# CAN_controller_trancs.net
KiCad netlist of a schematic drawn in Altium Designer
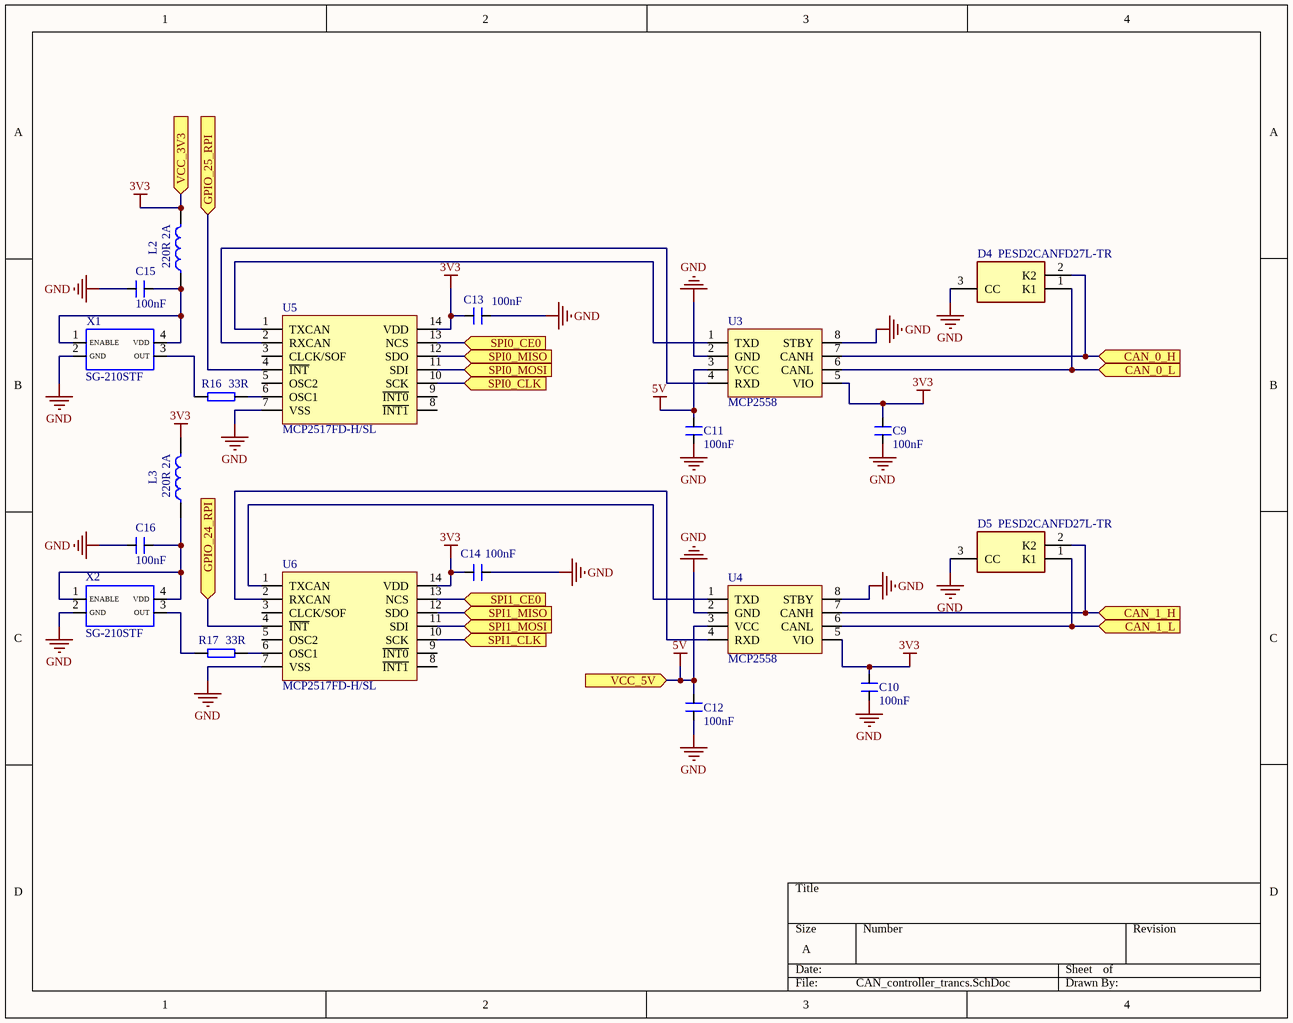
[diagram p0: CAN_controller_trancs.SchDoc]

(export (version "E")
  (design (tool "Eeschema 10.0.6"))
  (components
    (comp (ref "C9") (value "100nF") (footprint "CAP_0805") (libsource (lib "sch_comp") (part "CAP_0805")))
    (comp (ref "C10") (value "100nF") (footprint "CAP_0805") (libsource (lib "sch_comp") (part "CAP_0805")))
    (comp (ref "C11") (value "100nF") (footprint "CAP_0805") (libsource (lib "sch_comp") (part "CAP_0805")))
    (comp (ref "C12") (value "100nF") (footprint "CAP_0805") (libsource (lib "sch_comp") (part "CAP_0805")))
    (comp (ref "C13") (value "100nF") (footprint "CAP_0805") (libsource (lib "sch_comp") (part "CAP_0805")))
    (comp (ref "C14") (value "100nF") (footprint "CAP_0805") (libsource (lib "sch_comp") (part "CAP_0805")))
    (comp (ref "C15") (value "100nF") (footprint "CAP_0805") (libsource (lib "sch_comp") (part "CAP_0805")))
    (comp (ref "C16") (value "100nF") (footprint "CAP_0805") (libsource (lib "sch_comp") (part "CAP_0805")))
    (comp (ref "D4")
      (value "PESD2CANFD27L-TR")
      (footprint "SamacSys:SOT95P230X110-3N")
      (description "Diode")
      (fields (field (name "MOUSER PART NUMBER") "771-PESD2CANFD27L-TR"))
      (libsource (lib "*") (part "PESD2CANFD27L-TR"))
    )
    (comp (ref "D5")
      (value "PESD2CANFD27L-TR")
      (footprint "SamacSys:SOT95P230X110-3N")
      (description "Diode")
      (fields (field (name "MOUSER PART NUMBER") "771-PESD2CANFD27L-TR"))
      (libsource (lib "*") (part "PESD2CANFD27L-TR"))
    )
    (comp (ref "L2") (value "220R 2A") (footprint "L_0805") (libsource (lib "sch_comp") (part "Inductor")))
    (comp (ref "L3") (value "220R 2A") (footprint "L_0805") (libsource (lib "sch_comp") (part "Inductor")))
    (comp (ref "R16") (value "33R") (footprint "RES0402") (libsource (lib "sch_comp") (part "RES 0402")))
    (comp (ref "R17") (value "33R") (footprint "RES0402") (libsource (lib "sch_comp") (part "RES 0402")))
    (comp (ref "U3")
      (value "MCP2558")
      (footprint "MCP2557_SOIC8")
      (libsource (lib "sch_comp") (part "MCP2558"))
    )
    (comp (ref "U4")
      (value "MCP2558")
      (footprint "MCP2557_SOIC8")
      (libsource (lib "sch_comp") (part "MCP2558"))
    )
    (comp (ref "U5")
      (value "MCP2517FD-H/SL")
      (footprint "MCP2517FD_SOIC14")
      (libsource (lib "sch_comp") (part "MCP2517FD-H/SL"))
    )
    (comp (ref "U6")
      (value "MCP2517FD-H/SL")
      (footprint "MCP2517FD_SOIC14")
      (libsource (lib "sch_comp") (part "MCP2517FD-H/SL"))
    )
    (comp (ref "X1") (value "SG-210STF") (footprint "Osc") (libsource (lib "sch_comp") (part "SG-210STF")))
    (comp (ref "X2") (value "SG-210STF") (footprint "Osc") (libsource (lib "sch_comp") (part "SG-210STF")))
  )
  (nets
    (net (code "1") (name "/CAN_0_H") (class "Default")
      (node (ref "D4") (pin "2") (pinfunction "K2_2") (pintype "passive"))
      (node (ref "U3") (pin "7") (pinfunction "CANH_7") (pintype "passive"))
    )
    (net (code "2") (name "/CAN_0_L") (class "Default")
      (node (ref "D4") (pin "1") (pinfunction "K1_1") (pintype "passive"))
      (node (ref "U3") (pin "6") (pinfunction "CANL_6") (pintype "passive"))
    )
    (net (code "3") (name "/CAN_1_H") (class "Default")
      (node (ref "D5") (pin "2") (pinfunction "K2_2") (pintype "passive"))
      (node (ref "U4") (pin "7") (pinfunction "CANH_7") (pintype "passive"))
    )
    (net (code "4") (name "/CAN_1_L") (class "Default")
      (node (ref "D5") (pin "1") (pinfunction "K1_1") (pintype "passive"))
      (node (ref "U4") (pin "6") (pinfunction "CANL_6") (pintype "passive"))
    )
    (net (code "5") (name "/GPIO_24_RPI") (class "Default")
      (node (ref "U6") (pin "4") (pinfunction "~{INT}_4") (pintype "passive"))
    )
    (net (code "6") (name "/GPIO_25_RPI") (class "Default")
      (node (ref "U5") (pin "4") (pinfunction "~{INT}_4") (pintype "passive"))
    )
    (net (code "7") (name "/SPI0_CE0") (class "Default")
      (node (ref "U5") (pin "13") (pinfunction "NCS_13") (pintype "passive"))
    )
    (net (code "8") (name "/SPI0_CLK") (class "Default")
      (node (ref "U5") (pin "10") (pinfunction "SCK_10") (pintype "passive"))
    )
    (net (code "9") (name "/SPI0_MISO") (class "Default")
      (node (ref "U5") (pin "12") (pinfunction "SDO_12") (pintype "passive"))
    )
    (net (code "10") (name "/SPI0_MOSI") (class "Default")
      (node (ref "U5") (pin "11") (pinfunction "SDI_11") (pintype "passive"))
    )
    (net (code "11") (name "/SPI1_CE0") (class "Default")
      (node (ref "U6") (pin "13") (pinfunction "NCS_13") (pintype "passive"))
    )
    (net (code "12") (name "/SPI1_CLK") (class "Default")
      (node (ref "U6") (pin "10") (pinfunction "SCK_10") (pintype "passive"))
    )
    (net (code "13") (name "/SPI1_MISO") (class "Default")
      (node (ref "U6") (pin "12") (pinfunction "SDO_12") (pintype "passive"))
    )
    (net (code "14") (name "/SPI1_MOSI") (class "Default")
      (node (ref "U6") (pin "11") (pinfunction "SDI_11") (pintype "passive"))
    )
    (net (code "15") (name "3V3") (class "Default")
      (node (ref "C10") (pin "2") (pintype "passive"))
      (node (ref "C13") (pin "1") (pintype "passive"))
      (node (ref "C14") (pin "1") (pintype "passive"))
      (node (ref "C9") (pin "2") (pintype "passive"))
      (node (ref "L2") (pin "2") (pinfunction "2_2") (pintype "passive"))
      (node (ref "L3") (pin "2") (pinfunction "2_2") (pintype "passive"))
      (node (ref "U3") (pin "5") (pinfunction "VIO_5") (pintype "passive"))
      (node (ref "U4") (pin "5") (pinfunction "VIO_5") (pintype "passive"))
      (node (ref "U5") (pin "14") (pinfunction "VDD_14") (pintype "passive"))
      (node (ref "U6") (pin "14") (pinfunction "VDD_14") (pintype "passive"))
    )
    (net (code "16") (name "5V") (class "Default")
      (node (ref "C11") (pin "2") (pintype "passive"))
      (node (ref "C12") (pin "2") (pintype "passive"))
      (node (ref "U3") (pin "3") (pinfunction "VCC_3") (pintype "passive"))
      (node (ref "U4") (pin "3") (pinfunction "VCC_3") (pintype "passive"))
    )
    (net (code "17") (name "GND") (class "Default")
      (node (ref "C10") (pin "1") (pintype "passive"))
      (node (ref "C11") (pin "1") (pintype "passive"))
      (node (ref "C12") (pin "1") (pintype "passive"))
      (node (ref "C13") (pin "2") (pintype "passive"))
      (node (ref "C14") (pin "2") (pintype "passive"))
      (node (ref "C15") (pin "2") (pintype "passive"))
      (node (ref "C16") (pin "2") (pintype "passive"))
      (node (ref "C9") (pin "1") (pintype "passive"))
      (node (ref "D4") (pin "3") (pinfunction "CC_3") (pintype "passive"))
      (node (ref "D5") (pin "3") (pinfunction "CC_3") (pintype "passive"))
      (node (ref "U3") (pin "2") (pinfunction "GND_2") (pintype "passive"))
      (node (ref "U3") (pin "8") (pinfunction "STBY_8") (pintype "passive"))
      (node (ref "U4") (pin "2") (pinfunction "GND_2") (pintype "passive"))
      (node (ref "U4") (pin "8") (pinfunction "STBY_8") (pintype "passive"))
      (node (ref "U5") (pin "7") (pinfunction "VSS_7") (pintype "passive"))
      (node (ref "U6") (pin "7") (pinfunction "VSS_7") (pintype "passive"))
      (node (ref "X1") (pin "2") (pinfunction "GND_2") (pintype "passive"))
      (node (ref "X2") (pin "2") (pinfunction "GND_2") (pintype "passive"))
    )
    (net (code "18") (name "Net-(U3-RXD)") (class "Default")
      (node (ref "U3") (pin "4") (pinfunction "RXD_4") (pintype "passive"))
      (node (ref "U5") (pin "2") (pinfunction "RXCAN_2") (pintype "passive"))
    )
    (net (code "19") (name "Net-(U3-TXD)") (class "Default")
      (node (ref "U3") (pin "1") (pinfunction "TXD_1") (pintype "passive"))
      (node (ref "U5") (pin "1") (pinfunction "TXCAN_1") (pintype "passive"))
    )
    (net (code "20") (name "Net-(U4-RXD)") (class "Default")
      (node (ref "U4") (pin "4") (pinfunction "RXD_4") (pintype "passive"))
      (node (ref "U6") (pin "2") (pinfunction "RXCAN_2") (pintype "passive"))
    )
    (net (code "21") (name "Net-(U4-TXD)") (class "Default")
      (node (ref "U4") (pin "1") (pinfunction "TXD_1") (pintype "passive"))
      (node (ref "U6") (pin "1") (pinfunction "TXCAN_1") (pintype "passive"))
    )
    (net (code "22") (name "Net-(U5-OSC1)") (class "Default")
      (node (ref "R16") (pin "2") (pintype "passive"))
      (node (ref "U5") (pin "6") (pinfunction "OSC1_6") (pintype "passive"))
    )
    (net (code "23") (name "Net-(U6-OSC1)") (class "Default")
      (node (ref "R17") (pin "2") (pintype "passive"))
      (node (ref "U6") (pin "6") (pinfunction "OSC1_6") (pintype "passive"))
    )
    (net (code "24") (name "Net-(X1-ENABLE)") (class "Default")
      (node (ref "C15") (pin "1") (pintype "passive"))
      (node (ref "L2") (pin "1") (pinfunction "1_1") (pintype "passive"))
      (node (ref "X1") (pin "1") (pinfunction "ENABLE_1") (pintype "passive"))
      (node (ref "X1") (pin "4") (pinfunction "VDD_4") (pintype "passive"))
    )
    (net (code "25") (name "Net-(X1-OUT)") (class "Default")
      (node (ref "R16") (pin "1") (pintype "passive"))
      (node (ref "X1") (pin "3") (pinfunction "OUT_3") (pintype "passive"))
    )
    (net (code "26") (name "Net-(X2-ENABLE)") (class "Default")
      (node (ref "C16") (pin "1") (pintype "passive"))
      (node (ref "L3") (pin "1") (pinfunction "1_1") (pintype "passive"))
      (node (ref "X2") (pin "1") (pinfunction "ENABLE_1") (pintype "passive"))
      (node (ref "X2") (pin "4") (pinfunction "VDD_4") (pintype "passive"))
    )
    (net (code "27") (name "Net-(X2-OUT)") (class "Default")
      (node (ref "R17") (pin "1") (pintype "passive"))
      (node (ref "X2") (pin "3") (pinfunction "OUT_3") (pintype "passive"))
    )
    (net (code "28") (name "unconnected-(U5-CLCK{slash}SOF-Pad3)") (class "Default")
      (node (ref "U5") (pin "3") (pinfunction "CLCK/SOF_3") (pintype "passive"))
    )
    (net (code "29") (name "unconnected-(U5-OSC2-Pad5)") (class "Default")
      (node (ref "U5") (pin "5") (pinfunction "OSC2_5") (pintype "passive"))
    )
    (net (code "30") (name "unconnected-(U5-~{INT0}-Pad9)") (class "Default")
      (node (ref "U5") (pin "9") (pinfunction "~{INT0}_9") (pintype "passive"))
    )
    (net (code "31") (name "unconnected-(U5-~{INT1}-Pad8)") (class "Default")
      (node (ref "U5") (pin "8") (pinfunction "~{INT1}_8") (pintype "passive"))
    )
    (net (code "32") (name "unconnected-(U6-CLCK{slash}SOF-Pad3)") (class "Default")
      (node (ref "U6") (pin "3") (pinfunction "CLCK/SOF_3") (pintype "passive"))
    )
    (net (code "33") (name "unconnected-(U6-OSC2-Pad5)") (class "Default")
      (node (ref "U6") (pin "5") (pinfunction "OSC2_5") (pintype "passive"))
    )
    (net (code "34") (name "unconnected-(U6-~{INT0}-Pad9)") (class "Default")
      (node (ref "U6") (pin "9") (pinfunction "~{INT0}_9") (pintype "passive"))
    )
    (net (code "35") (name "unconnected-(U6-~{INT1}-Pad8)") (class "Default")
      (node (ref "U6") (pin "8") (pinfunction "~{INT1}_8") (pintype "passive"))
    )
  )
)
